# Adafruit_NeoPixel_Driver_BFF.net
KiCad netlist of a schematic drawn in EAGLE
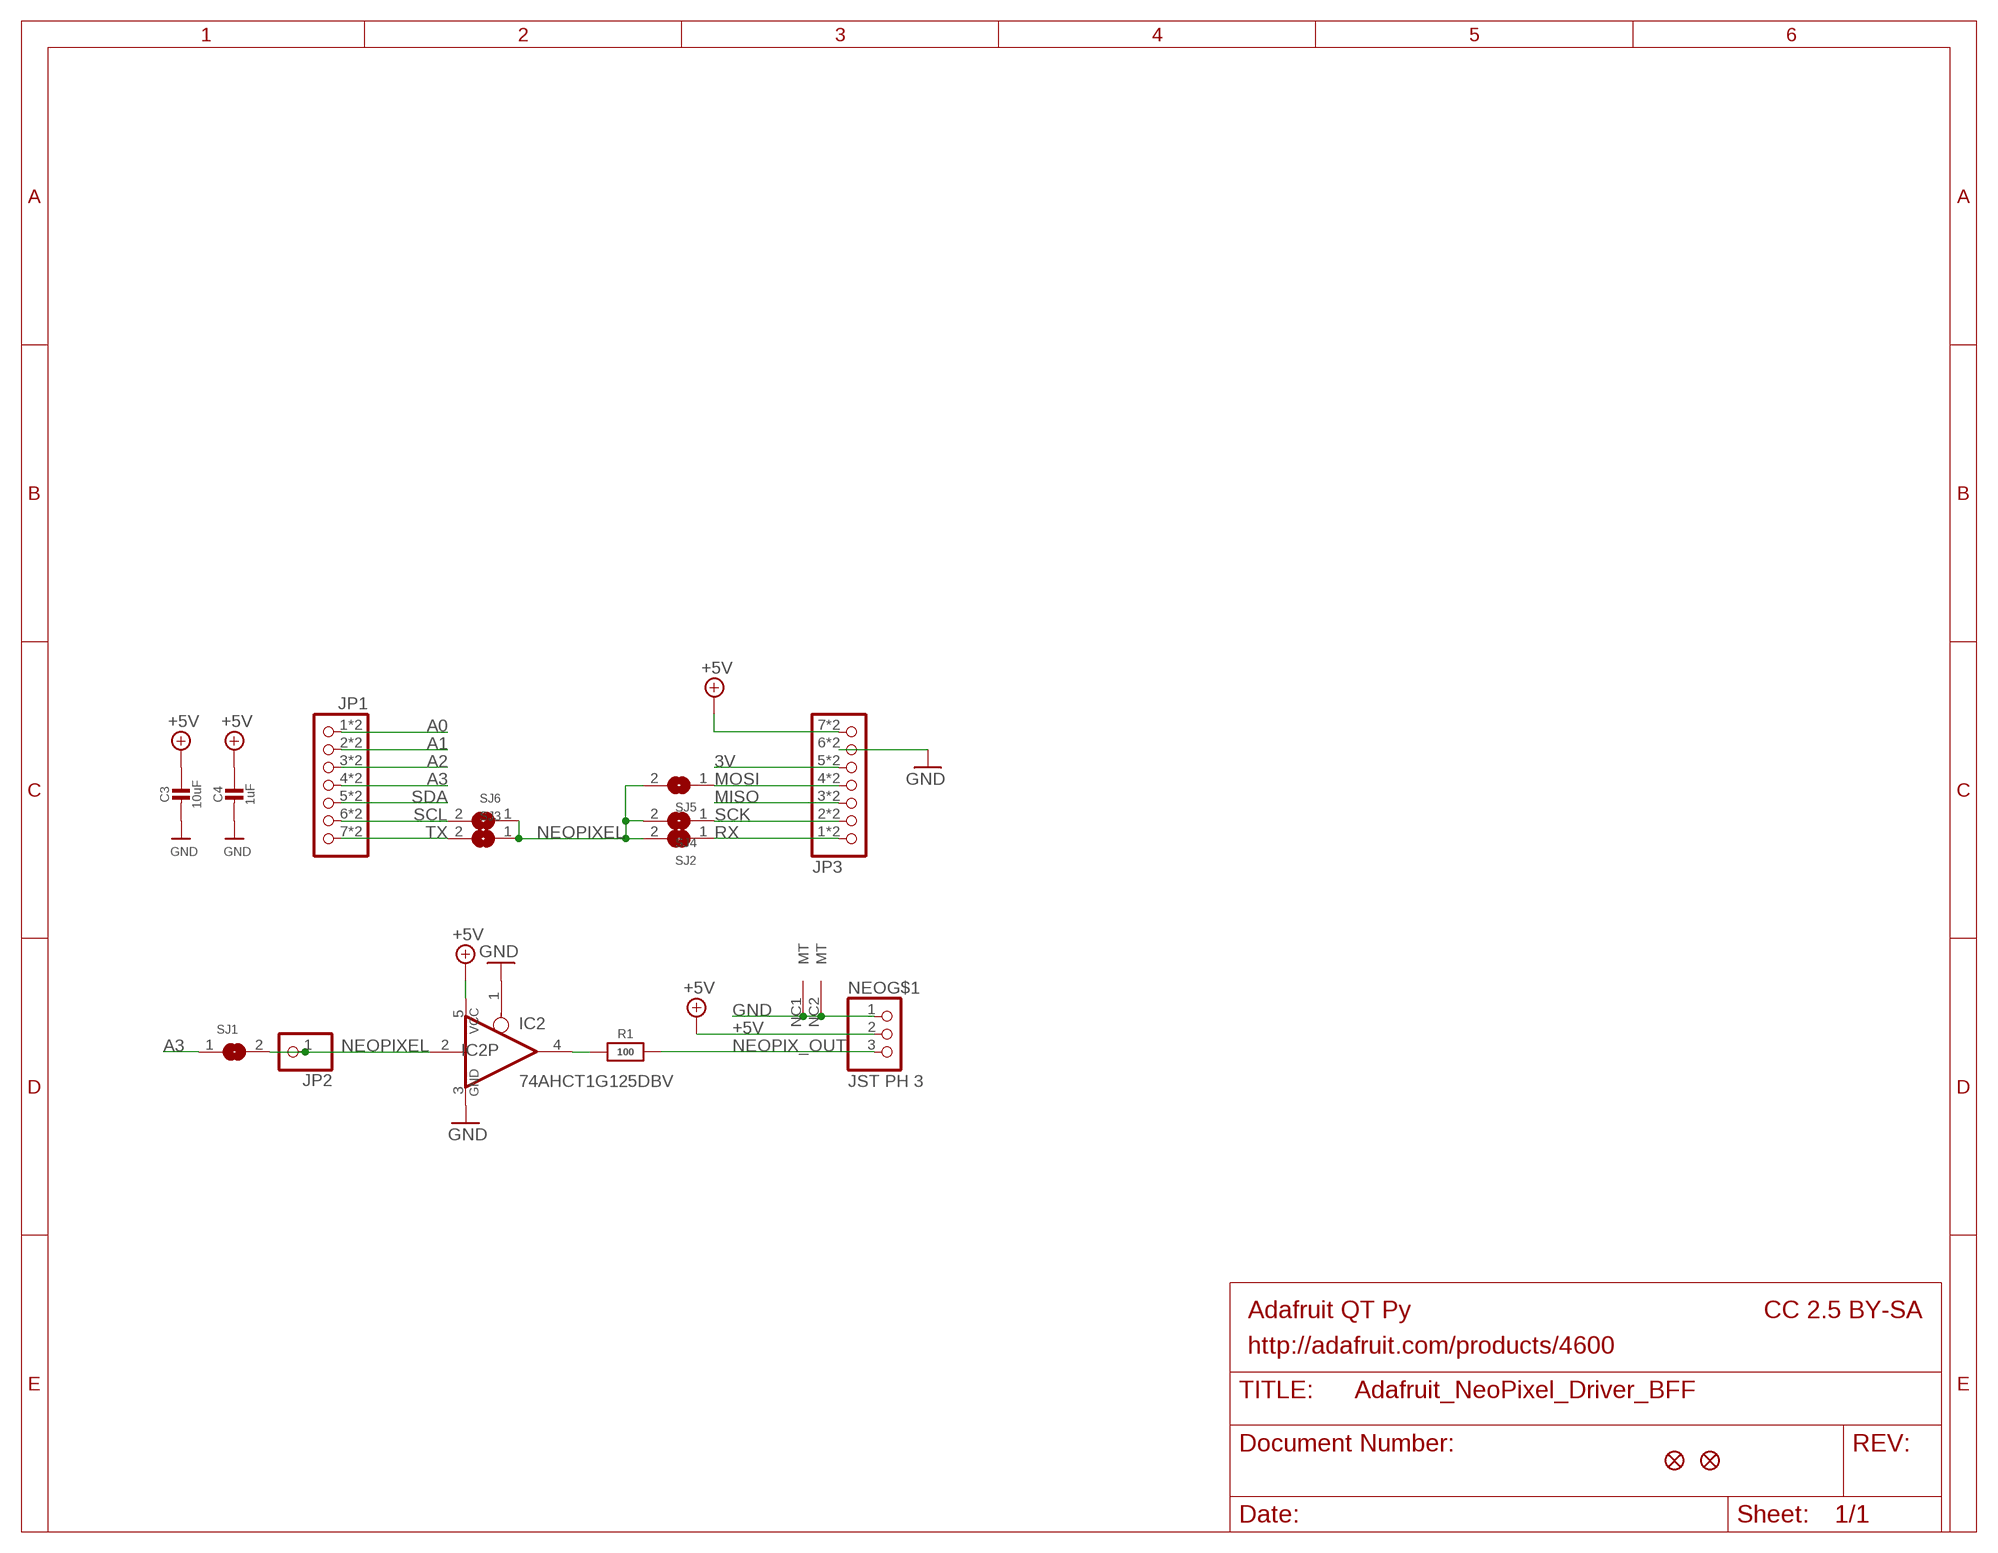
[diagram p0: schematic, sheet 1]

(export (version "E")
  (design (tool "Eeschema 10.0.6"))
  (components
    (comp (ref "C3")
      (value "10uF")
      (footprint "eagle-import:0805-NO")
      (libsource (lib "eagle-import") (part "CAP_CERAMIC0805-NOOUTLINE"))
    )
    (comp (ref "C4")
      (value "1uF")
      (footprint "eagle-import:0603-NO")
      (libsource (lib "eagle-import") (part "CAP_CERAMIC0603_NO"))
    )
    (comp (ref "IC2")
      (value "74AHCT1G125DBV")
      (footprint "eagle-import:SOT23-5")
      (libsource (lib "eagle-import") (part "741G125DBVAHCT"))
    )
    (comp (ref "JP1")
      (value "HEADER-1X7_CASTEL")
      (footprint "eagle-import:1X07_CASTEL")
      (libsource (lib "eagle-import") (part "HEADER-1X7_CASTEL"))
    )
    (comp (ref "JP2")
      (value "HEADER-1X1ROUND_76MIL")
      (footprint "eagle-import:1X01_ROUND_76MIL")
      (libsource (lib "eagle-import") (part "HEADER-1X1ROUND_76MIL"))
    )
    (comp (ref "JP3")
      (value "HEADER-1X7_CASTEL")
      (footprint "eagle-import:1X07_CASTEL")
      (libsource (lib "eagle-import") (part "HEADER-1X7_CASTEL"))
    )
    (comp (ref "NEO")
      (value "JST PH 3")
      (footprint "eagle-import:JSTPH3")
      (libsource (lib "eagle-import") (part "CON_JST_PH_3PIN"))
    )
    (comp (ref "R1")
      (value "100")
      (footprint "eagle-import:0603-NO")
      (libsource (lib "eagle-import") (part "RESISTOR_0603_NOOUT"))
    )
    (comp (ref "SJ1")
      (value "SOLDERJUMPERCLOSED")
      (footprint "eagle-import:SOLDERJUMPER_CLOSEDWIRE")
      (libsource (lib "eagle-import") (part "SOLDERJUMPERCLOSED"))
    )
    (comp (ref "SJ2")
      (value "SOLDERJUMPER")
      (footprint "eagle-import:SOLDERJUMPER_ARROW_NOPASTE")
      (libsource (lib "eagle-import") (part "SOLDERJUMPER"))
    )
    (comp (ref "SJ3")
      (value "SOLDERJUMPER")
      (footprint "eagle-import:SOLDERJUMPER_ARROW_NOPASTE")
      (libsource (lib "eagle-import") (part "SOLDERJUMPER"))
    )
    (comp (ref "SJ4")
      (value "SOLDERJUMPER")
      (footprint "eagle-import:SOLDERJUMPER_ARROW_NOPASTE")
      (libsource (lib "eagle-import") (part "SOLDERJUMPER"))
    )
    (comp (ref "SJ5")
      (value "SOLDERJUMPER")
      (footprint "eagle-import:SOLDERJUMPER_ARROW_NOPASTE")
      (libsource (lib "eagle-import") (part "SOLDERJUMPER"))
    )
    (comp (ref "SJ6")
      (value "SOLDERJUMPER")
      (footprint "eagle-import:SOLDERJUMPER_ARROW_NOPASTE")
      (libsource (lib "eagle-import") (part "SOLDERJUMPER"))
    )
    (comp (ref "U$6")
      (value "FIDUCIAL_1MM")
      (footprint "eagle-import:FIDUCIAL_1MM")
      (libsource (lib "eagle-import") (part "FIDUCIAL_1MM"))
    )
    (comp (ref "U$8")
      (value "FIDUCIAL_1MM")
      (footprint "eagle-import:FIDUCIAL_1MM")
      (libsource (lib "eagle-import") (part "FIDUCIAL_1MM"))
    )
  )
  (nets
    (net (code "1") (name "+5V") (class "Default")
      (node (ref "C3") (pin "1") (pinfunction "1_1") (pintype "passive"))
      (node (ref "C4") (pin "1") (pinfunction "1_1") (pintype "passive"))
      (node (ref "IC2") (pin "5") (pinfunction "VCC_5") (pintype "power_in"))
      (node (ref "JP3") (pin "7") (pinfunction "7_7") (pintype "passive"))
      (node (ref "JP3") (pin "7C") (pinfunction "7_7C") (pintype "passive"))
      (node (ref "NEO") (pin "2") (pinfunction "2_2") (pintype "passive"))
    )
    (net (code "2") (name "/3V") (class "Default")
      (node (ref "JP3") (pin "5") (pinfunction "5_5") (pintype "passive"))
      (node (ref "JP3") (pin "5C") (pinfunction "5_5C") (pintype "passive"))
    )
    (net (code "3") (name "/A0") (class "Default")
      (node (ref "JP1") (pin "1") (pinfunction "1_1") (pintype "passive"))
      (node (ref "JP1") (pin "1C") (pinfunction "1_1C") (pintype "passive"))
    )
    (net (code "4") (name "/A1") (class "Default")
      (node (ref "JP1") (pin "2") (pinfunction "2_2") (pintype "passive"))
      (node (ref "JP1") (pin "2C") (pinfunction "2_2C") (pintype "passive"))
    )
    (net (code "5") (name "/A2") (class "Default")
      (node (ref "JP1") (pin "3") (pinfunction "3_3") (pintype "passive"))
      (node (ref "JP1") (pin "3C") (pinfunction "3_3C") (pintype "passive"))
    )
    (net (code "6") (name "/A3") (class "Default")
      (node (ref "JP1") (pin "4") (pinfunction "4_4") (pintype "passive"))
      (node (ref "JP1") (pin "4C") (pinfunction "4_4C") (pintype "passive"))
      (node (ref "SJ1") (pin "1") (pinfunction "1_1") (pintype "passive"))
    )
    (net (code "7") (name "/MISO") (class "Default")
      (node (ref "JP3") (pin "3") (pinfunction "3_3") (pintype "passive"))
      (node (ref "JP3") (pin "3C") (pinfunction "3_3C") (pintype "passive"))
    )
    (net (code "8") (name "/MOSI") (class "Default")
      (node (ref "JP3") (pin "4") (pinfunction "4_4") (pintype "passive"))
      (node (ref "JP3") (pin "4C") (pinfunction "4_4C") (pintype "passive"))
      (node (ref "SJ5") (pin "1") (pinfunction "1_1") (pintype "passive"))
    )
    (net (code "9") (name "/NEOPIXEL") (class "Default")
      (node (ref "IC2") (pin "2") (pinfunction "I_2") (pintype "input"))
      (node (ref "JP2") (pin "1") (pinfunction "1_1") (pintype "passive"))
      (node (ref "SJ1") (pin "2") (pinfunction "2_2") (pintype "passive"))
      (node (ref "SJ2") (pin "2") (pinfunction "2_2") (pintype "passive"))
      (node (ref "SJ3") (pin "1") (pinfunction "1_1") (pintype "passive"))
      (node (ref "SJ4") (pin "2") (pinfunction "2_2") (pintype "passive"))
      (node (ref "SJ5") (pin "2") (pinfunction "2_2") (pintype "passive"))
      (node (ref "SJ6") (pin "1") (pinfunction "1_1") (pintype "passive"))
    )
    (net (code "10") (name "/NEOPIX_OUT") (class "Default")
      (node (ref "NEO") (pin "3") (pinfunction "3_3") (pintype "passive"))
      (node (ref "R1") (pin "2") (pinfunction "2_2") (pintype "passive"))
    )
    (net (code "11") (name "/RX") (class "Default")
      (node (ref "JP3") (pin "1") (pinfunction "1_1") (pintype "passive"))
      (node (ref "JP3") (pin "1C") (pinfunction "1_1C") (pintype "passive"))
      (node (ref "SJ2") (pin "1") (pinfunction "1_1") (pintype "passive"))
    )
    (net (code "12") (name "/SCK") (class "Default")
      (node (ref "JP3") (pin "2") (pinfunction "2_2") (pintype "passive"))
      (node (ref "JP3") (pin "2C") (pinfunction "2_2C") (pintype "passive"))
      (node (ref "SJ4") (pin "1") (pinfunction "1_1") (pintype "passive"))
    )
    (net (code "13") (name "/SCL") (class "Default")
      (node (ref "JP1") (pin "6") (pinfunction "6_6") (pintype "passive"))
      (node (ref "JP1") (pin "6C") (pinfunction "6_6C") (pintype "passive"))
      (node (ref "SJ6") (pin "2") (pinfunction "2_2") (pintype "passive"))
    )
    (net (code "14") (name "/SDA") (class "Default")
      (node (ref "JP1") (pin "5") (pinfunction "5_5") (pintype "passive"))
      (node (ref "JP1") (pin "5C") (pinfunction "5_5C") (pintype "passive"))
    )
    (net (code "15") (name "/TX") (class "Default")
      (node (ref "JP1") (pin "7") (pinfunction "7_7") (pintype "passive"))
      (node (ref "JP1") (pin "7C") (pinfunction "7_7C") (pintype "passive"))
      (node (ref "SJ3") (pin "2") (pinfunction "2_2") (pintype "passive"))
    )
    (net (code "16") (name "GND") (class "Default")
      (node (ref "C3") (pin "2") (pinfunction "2_2") (pintype "passive"))
      (node (ref "C4") (pin "2") (pinfunction "2_2") (pintype "passive"))
      (node (ref "IC2") (pin "1") (pinfunction "OE_1") (pintype "input"))
      (node (ref "IC2") (pin "3") (pinfunction "GND_3") (pintype "power_in"))
      (node (ref "JP3") (pin "6") (pinfunction "6_6") (pintype "passive"))
      (node (ref "JP3") (pin "6C") (pinfunction "6_6C") (pintype "passive"))
      (node (ref "NEO") (pin "1") (pinfunction "1_1") (pintype "passive"))
      (node (ref "NEO") (pin "NC1") (pinfunction "MT_NC1") (pintype "bidirectional"))
      (node (ref "NEO") (pin "NC2") (pinfunction "MT_NC2") (pintype "bidirectional"))
    )
    (net (code "17") (name "Net-(IC2A-O)") (class "Default")
      (node (ref "IC2") (pin "4") (pinfunction "O_4") (pintype "tri_state"))
      (node (ref "R1") (pin "1") (pinfunction "1_1") (pintype "passive"))
    )
  )
)
